# 2__Inverter.net
KiCad netlist of a schematic drawn in Altium Designer
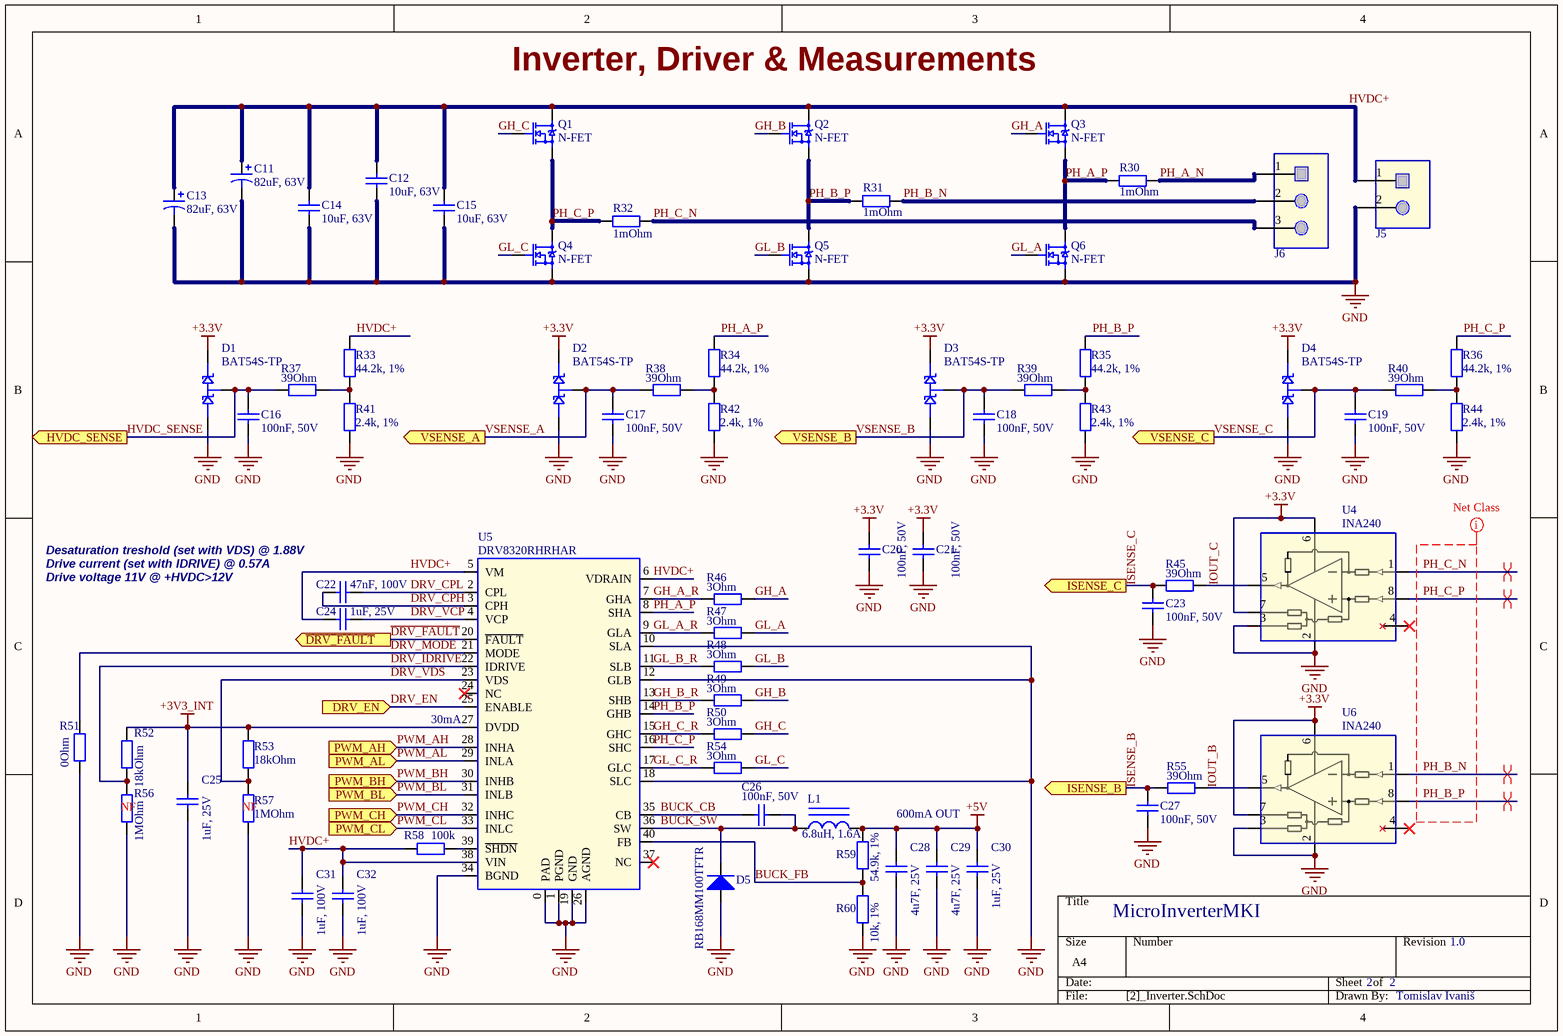
[diagram p0: [2]_Inverter.SchDoc]

(export (version "E")
  (design (tool "Eeschema 10.0.6"))
  (components
    (comp (ref "C11")
      (value "82uF, 63V")
      (footprint "CAP_H10")
      (description "Capacitor Polarized")
      (fields (field (name "MANUFACTURER PART NUMBER") "HHXC630ARA820MJA0G"))
      (libsource (lib "MyComponentLib") (part "Cap Pol"))
    )
    (comp (ref "C12")
      (value "10uF, 63V")
      (footprint "1210")
      (description "Capacitor")
      (fields (field (name "MANUFACTURER PART NUMBER") "GRM32ER71J106KA12L"))
      (libsource (lib "MyComponentLib") (part "Cap Semi"))
    )
    (comp (ref "C13")
      (value "82uF, 63V")
      (footprint "CAP_H10")
      (description "Capacitor Polarized")
      (fields (field (name "MANUFACTURER PART NUMBER") "HHXC630ARA820MJA0G"))
      (libsource (lib "MyComponentLib") (part "Cap Pol"))
    )
    (comp (ref "C14")
      (value "10uF, 63V")
      (footprint "1210")
      (description "Capacitor")
      (fields (field (name "MANUFACTURER PART NUMBER") "GRM32ER71J106KA12L"))
      (libsource (lib "MyComponentLib") (part "Cap Semi"))
    )
    (comp (ref "C15")
      (value "10uF, 63V")
      (footprint "1210")
      (description "Capacitor")
      (fields (field (name "MANUFACTURER PART NUMBER") "GRM32ER71J106KA12L"))
      (libsource (lib "MyComponentLib") (part "Cap Semi"))
    )
    (comp (ref "C16")
      (value "100nF, 50V")
      (footprint "0603")
      (description "Capacitor")
      (fields (field (name "MANUFACTURER PART NUMBER") "C0603C104M5RACTU"))
      (libsource (lib "MyComponentLib") (part "Cap Semi"))
    )
    (comp (ref "C17")
      (value "100nF, 50V")
      (footprint "0603")
      (description "Capacitor")
      (fields (field (name "MANUFACTURER PART NUMBER") "C0603C104M5RACTU"))
      (libsource (lib "MyComponentLib") (part "Cap Semi"))
    )
    (comp (ref "C18")
      (value "100nF, 50V")
      (footprint "0603")
      (description "Capacitor")
      (fields (field (name "MANUFACTURER PART NUMBER") "C0603C104M5RACTU"))
      (libsource (lib "MyComponentLib") (part "Cap Semi"))
    )
    (comp (ref "C19")
      (value "100nF, 50V")
      (footprint "0603")
      (description "Capacitor")
      (fields (field (name "MANUFACTURER PART NUMBER") "C0603C104M5RACTU"))
      (libsource (lib "MyComponentLib") (part "Cap Semi"))
    )
    (comp (ref "C20")
      (value "100nF, 50V")
      (footprint "0603")
      (description "Capacitor")
      (fields (field (name "MANUFACTURER PART NUMBER") "C0603C104M5RACTU"))
      (libsource (lib "MyComponentLib") (part "Cap Semi"))
    )
    (comp (ref "C21")
      (value "100nF, 50V")
      (footprint "0603")
      (description "Capacitor")
      (fields (field (name "MANUFACTURER PART NUMBER") "C0603C104M5RACTU"))
      (libsource (lib "MyComponentLib") (part "Cap Semi"))
    )
    (comp (ref "C22")
      (value "47nF, 100V")
      (footprint "0805")
      (description "Capacitor")
      (fields (field (name "MANUFACTURER PART NUMBER") "CC0805KKX7R0BB473"))
      (libsource (lib "MyComponentLib") (part "Cap Semi"))
    )
    (comp (ref "C23")
      (value "100nF, 50V")
      (footprint "0603")
      (description "Capacitor")
      (fields (field (name "MANUFACTURER PART NUMBER") "C0603C104M5RACTU"))
      (libsource (lib "MyComponentLib") (part "Cap Semi"))
    )
    (comp (ref "C24")
      (value "1uF, 25V")
      (footprint "0805")
      (description "Capacitor")
      (fields (field (name "MANUFACTURER PART NUMBER") "VJ0805Y105KXXTW1BC"))
      (libsource (lib "MyComponentLib") (part "Cap Semi"))
    )
    (comp (ref "C25")
      (value "1uF, 25V")
      (footprint "0805")
      (description "Capacitor")
      (fields (field (name "MANUFACTURER PART NUMBER") "VJ0805Y105KXXTW1BC"))
      (libsource (lib "MyComponentLib") (part "Cap Semi"))
    )
    (comp (ref "C26")
      (value "100nF, 50V")
      (footprint "0603")
      (description "Capacitor")
      (fields (field (name "MANUFACTURER PART NUMBER") "C0603C104M5RACTU"))
      (libsource (lib "MyComponentLib") (part "Cap Semi"))
    )
    (comp (ref "C27")
      (value "100nF, 50V")
      (footprint "0603")
      (description "Capacitor")
      (fields (field (name "MANUFACTURER PART NUMBER") "C0603C104M5RACTU"))
      (libsource (lib "MyComponentLib") (part "Cap Semi"))
    )
    (comp (ref "C28")
      (value "4u7F, 25V")
      (footprint "0805")
      (description "Capacitor")
      (fields (field (name "MANUFACTURER PART NUMBER") "885012107018"))
      (libsource (lib "MyComponentLib") (part "Cap Semi"))
    )
    (comp (ref "C29")
      (value "4u7F, 25V")
      (footprint "0805")
      (description "Capacitor")
      (fields (field (name "MANUFACTURER PART NUMBER") "885012107018"))
      (libsource (lib "MyComponentLib") (part "Cap Semi"))
    )
    (comp (ref "C30")
      (value "1uF, 25V")
      (footprint "0805")
      (description "Capacitor")
      (fields (field (name "MANUFACTURER PART NUMBER") "VJ0805Y105KXXTW1BC"))
      (libsource (lib "MyComponentLib") (part "Cap Semi"))
    )
    (comp (ref "C31")
      (value "1uF, 100V")
      (footprint "0805")
      (description "Capacitor")
      (fields (field (name "MANUFACTURER PART NUMBER") "HMK212BBJ105KG-TE"))
      (libsource (lib "MyComponentLib") (part "Cap Semi"))
    )
    (comp (ref "C32")
      (value "1uF, 100V")
      (footprint "0805")
      (description "Capacitor")
      (fields (field (name "MANUFACTURER PART NUMBER") "HMK212BBJ105KG-TE"))
      (libsource (lib "MyComponentLib") (part "Cap Semi"))
    )
    (comp (ref "D1")
      (value "BAT54S-TP")
      (footprint "SOT 23")
      (libsource (lib "MyComponentLib") (part "BAT54S-TP"))
    )
    (comp (ref "D2")
      (value "BAT54S-TP")
      (footprint "SOT 23")
      (libsource (lib "MyComponentLib") (part "BAT54S-TP"))
    )
    (comp (ref "D3")
      (value "BAT54S-TP")
      (footprint "SOT 23")
      (libsource (lib "MyComponentLib") (part "BAT54S-TP"))
    )
    (comp (ref "D4")
      (value "BAT54S-TP")
      (footprint "SOT 23")
      (libsource (lib "MyComponentLib") (part "BAT54S-TP"))
    )
    (comp (ref "D5")
      (value "RB168MM100TFTR")
      (footprint "SOD123")
      (libsource (lib "MyComponentLib") (part "Diode"))
    )
    (comp (ref "J5")
      (value "TERMINAL 2")
      (footprint "TERMINAL 2 POS")
      (description "TERMINAL BLOCK 2 POS")
      (libsource (lib "MyComponentLib") (part "TERMINAL 2"))
    )
    (comp (ref "J6")
      (value "TERMINAL 3")
      (footprint "TERMINAL 3 POS")
      (description "TERMINAL BLOCK 3 POS")
      (libsource (lib "MyComponentLib") (part "TERMINAL 3"))
    )
    (comp (ref "L1")
      (value "6.8uH, 1.6A")
      (footprint "INDUCTOR - 4x4 mm")
      (description "Magnetic-Core Inductor")
      (fields (field (name "MANUFACTURER PART NUMBER") "TYS40306R8M-10"))
      (libsource (lib "MyComponentLib") (part "Inductor Iron"))
    )
    (comp (ref "Q1")
      (value "N-FET")
      (footprint "SO-8FL")
      (fields (field (name "MANUFACTURER PART NUMBER") "NVMFS6H800NT1G"))
      (libsource (lib "MyComponentLib") (part "N-FET"))
    )
    (comp (ref "Q2")
      (value "N-FET")
      (footprint "SO-8FL")
      (fields (field (name "MANUFACTURER PART NUMBER") "NVMFS6H800NT1G"))
      (libsource (lib "MyComponentLib") (part "N-FET"))
    )
    (comp (ref "Q3")
      (value "N-FET")
      (footprint "SO-8FL")
      (fields (field (name "MANUFACTURER PART NUMBER") "NVMFS6H800NT1G"))
      (libsource (lib "MyComponentLib") (part "N-FET"))
    )
    (comp (ref "Q4")
      (value "N-FET")
      (footprint "SO-8FL")
      (fields (field (name "MANUFACTURER PART NUMBER") "NVMFS6H800NT1G"))
      (libsource (lib "MyComponentLib") (part "N-FET"))
    )
    (comp (ref "Q5")
      (value "N-FET")
      (footprint "SO-8FL")
      (fields (field (name "MANUFACTURER PART NUMBER") "NVMFS6H800NT1G"))
      (libsource (lib "MyComponentLib") (part "N-FET"))
    )
    (comp (ref "Q6")
      (value "N-FET")
      (footprint "SO-8FL")
      (fields (field (name "MANUFACTURER PART NUMBER") "NVMFS6H800NT1G"))
      (libsource (lib "MyComponentLib") (part "N-FET"))
    )
    (comp (ref "R30")
      (value "1mOhm")
      (footprint "RES TLR2HW CURRENT SENSE")
      (description "Resistor")
      (fields (field (name "MANUFACTURER PART NUMBER") "TLR2HWDTE1L00F50"))
      (libsource (lib "") (part "Res_1"))
    )
    (comp (ref "R31")
      (value "1mOhm")
      (footprint "RES TLR2HW CURRENT SENSE")
      (description "Resistor")
      (fields (field (name "MANUFACTURER PART NUMBER") "TLR2HWDTE1L00F50"))
      (libsource (lib "") (part "Res_1"))
    )
    (comp (ref "R32")
      (value "1mOhm")
      (footprint "RES TLR2HW CURRENT SENSE")
      (description "Resistor")
      (fields (field (name "MANUFACTURER PART NUMBER") "TLR2HWDTE1L00F50"))
      (libsource (lib "") (part "Res_1"))
    )
    (comp (ref "R33")
      (value "44.2k, 1%")
      (footprint "0805")
      (description "Resistor")
      (fields (field (name "MANUFACTURER PART NUMBER") "CR0805-FX-4422ELF"))
      (libsource (lib "MyComponentLib") (part "Res"))
    )
    (comp (ref "R34")
      (value "44.2k, 1%")
      (footprint "0805")
      (description "Resistor")
      (fields (field (name "MANUFACTURER PART NUMBER") "CR0805-FX-4422ELF"))
      (libsource (lib "MyComponentLib") (part "Res"))
    )
    (comp (ref "R35")
      (value "44.2k, 1%")
      (footprint "0805")
      (description "Resistor")
      (fields (field (name "MANUFACTURER PART NUMBER") "CR0805-FX-4422ELF"))
      (libsource (lib "MyComponentLib") (part "Res"))
    )
    (comp (ref "R36")
      (value "44.2k, 1%")
      (footprint "0805")
      (description "Resistor")
      (fields (field (name "MANUFACTURER PART NUMBER") "CR0805-FX-4422ELF"))
      (libsource (lib "MyComponentLib") (part "Res"))
    )
    (comp (ref "R37")
      (value "39Ohm")
      (footprint "0805")
      (description "Resistor")
      (fields (field (name "MANUFACTURER PART NUMBER") "CR0805-JW-390ELF"))
      (libsource (lib "") (part "Res_1"))
    )
    (comp (ref "R38")
      (value "39Ohm")
      (footprint "0805")
      (description "Resistor")
      (fields (field (name "MANUFACTURER PART NUMBER") "CR0805-JW-390ELF"))
      (libsource (lib "") (part "Res_1"))
    )
    (comp (ref "R39")
      (value "39Ohm")
      (footprint "0805")
      (description "Resistor")
      (fields (field (name "MANUFACTURER PART NUMBER") "CR0805-JW-390ELF"))
      (libsource (lib "") (part "Res_1"))
    )
    (comp (ref "R40")
      (value "39Ohm")
      (footprint "0805")
      (description "Resistor")
      (fields (field (name "MANUFACTURER PART NUMBER") "CR0805-JW-390ELF"))
      (libsource (lib "") (part "Res_1"))
    )
    (comp (ref "R41")
      (value "2.4k, 1%")
      (footprint "0805")
      (description "Resistor")
      (fields (field (name "MANUFACTURER PART NUMBER") "CR0805-FX-2401ELF"))
      (libsource (lib "MyComponentLib") (part "Res"))
    )
    (comp (ref "R42")
      (value "2.4k, 1%")
      (footprint "0805")
      (description "Resistor")
      (fields (field (name "MANUFACTURER PART NUMBER") "CR0805-FX-2401ELF"))
      (libsource (lib "MyComponentLib") (part "Res"))
    )
    (comp (ref "R43")
      (value "2.4k, 1%")
      (footprint "0805")
      (description "Resistor")
      (fields (field (name "MANUFACTURER PART NUMBER") "CR0805-FX-2401ELF"))
      (libsource (lib "MyComponentLib") (part "Res"))
    )
    (comp (ref "R44")
      (value "2.4k, 1%")
      (footprint "0805")
      (description "Resistor")
      (fields (field (name "MANUFACTURER PART NUMBER") "CR0805-FX-2401ELF"))
      (libsource (lib "MyComponentLib") (part "Res"))
    )
    (comp (ref "R45")
      (value "39Ohm")
      (footprint "0805")
      (description "Resistor")
      (fields (field (name "MANUFACTURER PART NUMBER") "CR0805-JW-390ELF"))
      (libsource (lib "") (part "Res_1"))
    )
    (comp (ref "R46")
      (value "3Ohm")
      (footprint "0805")
      (description "Resistor")
      (fields (field (name "MANUFACTURER PART NUMBER") "SG73P2ATTD3R00F"))
      (libsource (lib "") (part "Res_1"))
    )
    (comp (ref "R47")
      (value "3Ohm")
      (footprint "0805")
      (description "Resistor")
      (fields (field (name "MANUFACTURER PART NUMBER") "SG73P2ATTD3R00F"))
      (libsource (lib "") (part "Res_1"))
    )
    (comp (ref "R48")
      (value "3Ohm")
      (footprint "0805")
      (description "Resistor")
      (fields (field (name "MANUFACTURER PART NUMBER") "SG73P2ATTD3R00F"))
      (libsource (lib "") (part "Res_1"))
    )
    (comp (ref "R49")
      (value "3Ohm")
      (footprint "0805")
      (description "Resistor")
      (fields (field (name "MANUFACTURER PART NUMBER") "SG73P2ATTD3R00F"))
      (libsource (lib "") (part "Res_1"))
    )
    (comp (ref "R50")
      (value "3Ohm")
      (footprint "0805")
      (description "Resistor")
      (fields (field (name "MANUFACTURER PART NUMBER") "SG73P2ATTD3R00F"))
      (libsource (lib "") (part "Res_1"))
    )
    (comp (ref "R51")
      (value "0Ohm")
      (footprint "0805")
      (description "Resistor")
      (fields (field (name "MANUFACTURER PART NUMBER") "CR0805-J/-000ELF"))
      (libsource (lib "MyComponentLib") (part "Res"))
    )
    (comp (ref "R52")
      (value "18kOhm")
      (footprint "0805")
      (description "Resistor")
      (fields (field (name "MANUFACTURER PART NUMBER") "CR0805-FX-1802ELF"))
      (libsource (lib "MyComponentLib") (part "Res"))
    )
    (comp (ref "R53")
      (value "18kOhm")
      (footprint "0805")
      (description "Resistor")
      (fields (field (name "MANUFACTURER PART NUMBER") "CR0805-FX-1802ELF"))
      (libsource (lib "MyComponentLib") (part "Res"))
    )
    (comp (ref "R54")
      (value "3Ohm")
      (footprint "0805")
      (description "Resistor")
      (fields (field (name "MANUFACTURER PART NUMBER") "SG73P2ATTD3R00F"))
      (libsource (lib "") (part "Res_1"))
    )
    (comp (ref "R55")
      (value "39Ohm")
      (footprint "0805")
      (description "Resistor")
      (fields (field (name "MANUFACTURER PART NUMBER") "CR0805-JW-390ELF"))
      (libsource (lib "") (part "Res_1"))
    )
    (comp (ref "R56")
      (value "1MOhm")
      (footprint "0805")
      (description "Resistor")
      (fields (field (name "MANUFACTURER PART NUMBER") "CR0805-FW-1005ELF"))
      (libsource (lib "MyComponentLib") (part "Res"))
    )
    (comp (ref "R57")
      (value "1MOhm")
      (footprint "0805")
      (description "Resistor")
      (fields (field (name "MANUFACTURER PART NUMBER") "CR0805-FW-1005ELF"))
      (libsource (lib "MyComponentLib") (part "Res"))
    )
    (comp (ref "R58")
      (value "100k")
      (footprint "0805")
      (description "Resistor")
      (fields (field (name "MANUFACTURER PART NUMBER") "CR0805-FX-1003ELF"))
      (libsource (lib "") (part "Res_2"))
    )
    (comp (ref "R59")
      (value "54.9k, 1%")
      (footprint "0805")
      (description "Resistor")
      (fields (field (name "MANUFACTURER PART NUMBER") "CR0805-FX-5492ELF"))
      (libsource (lib "MyComponentLib") (part "Res"))
    )
    (comp (ref "R60")
      (value "10k, 1%")
      (footprint "0805")
      (description "Resistor")
      (fields (field (name "MANUFACTURER PART NUMBER") "CR0805-FX-1002ELF"))
      (libsource (lib "MyComponentLib") (part "Res"))
    )
    (comp (ref "U4")
      (value "INA240")
      (footprint "SO 8 - HighDensity")
      (fields (field (name "MANUFACTURER PART NUMBER") "INA240A2DR"))
      (libsource (lib "MyComponentLib") (part "INA240"))
    )
    (comp (ref "U5")
      (value "DRV8320RHRHAR")
      (footprint "VQFN-40")
      (description "3f Gate driver 60V")
      (libsource (lib "MyComponentLib") (part "DRV8320RHRHAR"))
    )
    (comp (ref "U6")
      (value "INA240")
      (footprint "SO 8 - HighDensity")
      (fields (field (name "MANUFACTURER PART NUMBER") "INA240A2DR"))
      (libsource (lib "MyComponentLib") (part "INA240"))
    )
  )
  (nets
    (net (code "1") (name "+3.3V") (class "Default")
      (node (ref "C20") (pin "1") (pinfunction "1_1") (pintype "passive"))
      (node (ref "C21") (pin "1") (pinfunction "1_1") (pintype "passive"))
      (node (ref "D1") (pin "3") (pinfunction "K_3") (pintype "passive"))
      (node (ref "D2") (pin "3") (pinfunction "K_3") (pintype "passive"))
      (node (ref "D3") (pin "3") (pinfunction "K_3") (pintype "passive"))
      (node (ref "D4") (pin "3") (pinfunction "K_3") (pintype "passive"))
      (node (ref "U4") (pin "6") (pinfunction "*_6") (pintype "passive"))
      (node (ref "U4") (pin "7") (pinfunction "*_7") (pintype "passive"))
      (node (ref "U6") (pin "6") (pinfunction "*_6") (pintype "passive"))
      (node (ref "U6") (pin "7") (pinfunction "*_7") (pintype "passive"))
    )
    (net (code "2") (name "+3V3_INT") (class "Default")
      (node (ref "C25") (pin "1") (pinfunction "1_1") (pintype "passive"))
      (node (ref "R52") (pin "2") (pinfunction "2_2") (pintype "passive"))
      (node (ref "R53") (pin "2") (pinfunction "2_2") (pintype "passive"))
      (node (ref "U5") (pin "27") (pinfunction "DVDD_27") (pintype "passive"))
    )
    (net (code "3") (name "+5V") (class "Default")
      (node (ref "C28") (pin "1") (pinfunction "1_1") (pintype "passive"))
      (node (ref "C29") (pin "1") (pinfunction "1_1") (pintype "passive"))
      (node (ref "C30") (pin "1") (pinfunction "1_1") (pintype "passive"))
      (node (ref "L1") (pin "2") (pinfunction "2_2") (pintype "passive"))
      (node (ref "R59") (pin "2") (pinfunction "2_2") (pintype "passive"))
    )
    (net (code "4") (name "/BUCK_CB") (class "Default")
      (node (ref "C26") (pin "2") (pinfunction "2_2") (pintype "passive"))
      (node (ref "U5") (pin "35") (pinfunction "CB_35") (pintype "passive"))
    )
    (net (code "5") (name "/BUCK_FB") (class "Default")
      (node (ref "R59") (pin "1") (pinfunction "1_1") (pintype "passive"))
      (node (ref "R60") (pin "2") (pinfunction "2_2") (pintype "passive"))
      (node (ref "U5") (pin "40") (pinfunction "FB_40") (pintype "passive"))
    )
    (net (code "6") (name "/BUCK_SW") (class "Default")
      (node (ref "C26") (pin "1") (pinfunction "1_1") (pintype "passive"))
      (node (ref "D5") (pin "2") (pinfunction "K_2") (pintype "passive"))
      (node (ref "L1") (pin "1") (pinfunction "1_1") (pintype "passive"))
      (node (ref "U5") (pin "36") (pinfunction "SW_36") (pintype "passive"))
    )
    (net (code "7") (name "/DRV_CPH") (class "Default")
      (node (ref "C22") (pin "1") (pinfunction "1_1") (pintype "passive"))
      (node (ref "U5") (pin "3") (pinfunction "CPH_3") (pintype "passive"))
    )
    (net (code "8") (name "/DRV_CPL") (class "Default")
      (node (ref "C22") (pin "2") (pinfunction "2_2") (pintype "passive"))
      (node (ref "U5") (pin "2") (pinfunction "CPL_2") (pintype "passive"))
    )
    (net (code "9") (name "/DRV_EN") (class "Default")
      (node (ref "U5") (pin "25") (pinfunction "ENABLE_25") (pintype "passive"))
    )
    (net (code "10") (name "/DRV_IDRIVE") (class "Default")
      (node (ref "R52") (pin "1") (pinfunction "1_1") (pintype "passive"))
      (node (ref "R56") (pin "2") (pinfunction "2_2") (pintype "passive"))
      (node (ref "U5") (pin "22") (pinfunction "IDRIVE_22") (pintype "passive"))
    )
    (net (code "11") (name "/DRV_MODE") (class "Default")
      (node (ref "R51") (pin "2") (pinfunction "2_2") (pintype "passive"))
      (node (ref "U5") (pin "21") (pinfunction "MODE_21") (pintype "passive"))
    )
    (net (code "12") (name "/DRV_VCP") (class "Default")
      (node (ref "C24") (pin "1") (pinfunction "1_1") (pintype "passive"))
      (node (ref "U5") (pin "4") (pinfunction "VCP_4") (pintype "passive"))
    )
    (net (code "13") (name "/DRV_VDS") (class "Default")
      (node (ref "R53") (pin "1") (pinfunction "1_1") (pintype "passive"))
      (node (ref "R57") (pin "2") (pinfunction "2_2") (pintype "passive"))
      (node (ref "U5") (pin "23") (pinfunction "VDS_23") (pintype "passive"))
    )
    (net (code "14") (name "/GH_A") (class "Default")
      (node (ref "Q3") (pin "1") (pintype "passive"))
      (node (ref "R46") (pin "2") (pinfunction "2_2") (pintype "passive"))
    )
    (net (code "15") (name "/GH_A_R") (class "Default")
      (node (ref "R46") (pin "1") (pinfunction "1_1") (pintype "passive"))
      (node (ref "U5") (pin "7") (pinfunction "GHA_7") (pintype "passive"))
    )
    (net (code "16") (name "/GH_B") (class "Default")
      (node (ref "Q2") (pin "1") (pintype "passive"))
      (node (ref "R49") (pin "2") (pinfunction "2_2") (pintype "passive"))
    )
    (net (code "17") (name "/GH_B_R") (class "Default")
      (node (ref "R49") (pin "1") (pinfunction "1_1") (pintype "passive"))
      (node (ref "U5") (pin "13") (pinfunction "SHB_13") (pintype "passive"))
    )
    (net (code "18") (name "/GH_C") (class "Default")
      (node (ref "Q1") (pin "1") (pintype "passive"))
      (node (ref "R50") (pin "2") (pinfunction "2_2") (pintype "passive"))
    )
    (net (code "19") (name "/GH_C_R") (class "Default")
      (node (ref "R50") (pin "1") (pinfunction "1_1") (pintype "passive"))
      (node (ref "U5") (pin "15") (pinfunction "GHC_15") (pintype "passive"))
    )
    (net (code "20") (name "/GL_A") (class "Default")
      (node (ref "Q6") (pin "1") (pintype "passive"))
      (node (ref "R47") (pin "2") (pinfunction "2_2") (pintype "passive"))
    )
    (net (code "21") (name "/GL_A_R") (class "Default")
      (node (ref "R47") (pin "1") (pinfunction "1_1") (pintype "passive"))
      (node (ref "U5") (pin "9") (pinfunction "GLA_9") (pintype "passive"))
    )
    (net (code "22") (name "/GL_B") (class "Default")
      (node (ref "Q5") (pin "1") (pintype "passive"))
      (node (ref "R48") (pin "2") (pinfunction "2_2") (pintype "passive"))
    )
    (net (code "23") (name "/GL_B_R") (class "Default")
      (node (ref "R48") (pin "1") (pinfunction "1_1") (pintype "passive"))
      (node (ref "U5") (pin "11") (pinfunction "SLB_11") (pintype "passive"))
    )
    (net (code "24") (name "/GL_C") (class "Default")
      (node (ref "Q4") (pin "1") (pintype "passive"))
      (node (ref "R54") (pin "2") (pinfunction "2_2") (pintype "passive"))
    )
    (net (code "25") (name "/GL_C_R") (class "Default")
      (node (ref "R54") (pin "1") (pinfunction "1_1") (pintype "passive"))
      (node (ref "U5") (pin "17") (pinfunction "GLC_17") (pintype "passive"))
    )
    (net (code "26") (name "/HVDC+") (class "Default")
      (node (ref "C11") (pin "2") (pinfunction "1_2") (pintype "passive"))
      (node (ref "C12") (pin "1") (pinfunction "1_1") (pintype "passive"))
      (node (ref "C13") (pin "2") (pinfunction "1_2") (pintype "passive"))
      (node (ref "C14") (pin "1") (pinfunction "1_1") (pintype "passive"))
      (node (ref "C15") (pin "1") (pinfunction "1_1") (pintype "passive"))
      (node (ref "C24") (pin "2") (pinfunction "2_2") (pintype "passive"))
      (node (ref "C31") (pin "1") (pinfunction "1_1") (pintype "passive"))
      (node (ref "C32") (pin "1") (pinfunction "1_1") (pintype "passive"))
      (node (ref "J5") (pin "1") (pinfunction "1_1") (pintype "passive"))
      (node (ref "Q1") (pin "2") (pintype "passive"))
      (node (ref "Q2") (pin "2") (pintype "passive"))
      (node (ref "Q3") (pin "2") (pintype "passive"))
      (node (ref "R33") (pin "2") (pinfunction "2_2") (pintype "passive"))
      (node (ref "R58") (pin "2") (pinfunction "2_2") (pintype "passive"))
      (node (ref "U5") (pin "38") (pinfunction "VIN_38") (pintype "passive"))
      (node (ref "U5") (pin "5") (pinfunction "VM_5") (pintype "passive"))
      (node (ref "U5") (pin "6") (pinfunction "VDRAIN_6") (pintype "passive"))
    )
    (net (code "27") (name "/HVDC_SENSE") (class "Default")
      (node (ref "C16") (pin "1") (pinfunction "1_1") (pintype "passive"))
      (node (ref "D1") (pin "1") (pinfunction "KA_1") (pintype "passive"))
      (node (ref "R37") (pin "1") (pinfunction "1_1") (pintype "passive"))
    )
    (net (code "28") (name "/IOUT_B") (class "Default")
      (node (ref "R55") (pin "2") (pinfunction "2_2") (pintype "passive"))
      (node (ref "U6") (pin "5") (pinfunction "OUT_5") (pintype "output"))
    )
    (net (code "29") (name "/IOUT_C") (class "Default")
      (node (ref "R45") (pin "2") (pinfunction "2_2") (pintype "passive"))
      (node (ref "U4") (pin "5") (pinfunction "OUT_5") (pintype "output"))
    )
    (net (code "30") (name "/ISENSE_B") (class "Default")
      (node (ref "C27") (pin "1") (pinfunction "1_1") (pintype "passive"))
      (node (ref "R55") (pin "1") (pinfunction "1_1") (pintype "passive"))
    )
    (net (code "31") (name "/ISENSE_C") (class "Default")
      (node (ref "C23") (pin "1") (pinfunction "1_1") (pintype "passive"))
      (node (ref "R45") (pin "1") (pinfunction "1_1") (pintype "passive"))
    )
    (net (code "32") (name "/PH_A_N") (class "Default")
      (node (ref "J6") (pin "1") (pinfunction "1_1") (pintype "passive"))
      (node (ref "R30") (pin "2") (pinfunction "2_2") (pintype "passive"))
    )
    (net (code "33") (name "/PH_A_P") (class "Default")
      (node (ref "Q3") (pin "3") (pintype "passive"))
      (node (ref "Q6") (pin "2") (pintype "passive"))
      (node (ref "R30") (pin "1") (pinfunction "1_1") (pintype "passive"))
      (node (ref "R34") (pin "2") (pinfunction "2_2") (pintype "passive"))
      (node (ref "U5") (pin "8") (pinfunction "SHA_8") (pintype "passive"))
    )
    (net (code "34") (name "/PH_B_N") (class "Default")
      (node (ref "J6") (pin "2") (pinfunction "2_2") (pintype "passive"))
      (node (ref "R31") (pin "2") (pinfunction "2_2") (pintype "passive"))
      (node (ref "U6") (pin "1") (pinfunction "IN-_1") (pintype "input"))
    )
    (net (code "35") (name "/PH_B_P") (class "Default")
      (node (ref "Q2") (pin "3") (pintype "passive"))
      (node (ref "Q5") (pin "2") (pintype "passive"))
      (node (ref "R31") (pin "1") (pinfunction "1_1") (pintype "passive"))
      (node (ref "R35") (pin "2") (pinfunction "2_2") (pintype "passive"))
      (node (ref "U5") (pin "14") (pinfunction "GHB_14") (pintype "passive"))
      (node (ref "U6") (pin "8") (pinfunction "IN+_8") (pintype "input"))
    )
    (net (code "36") (name "/PH_C_N") (class "Default")
      (node (ref "J6") (pin "3") (pinfunction "3_3") (pintype "passive"))
      (node (ref "R32") (pin "2") (pinfunction "2_2") (pintype "passive"))
      (node (ref "U4") (pin "1") (pinfunction "IN-_1") (pintype "input"))
    )
    (net (code "37") (name "/PH_C_P") (class "Default")
      (node (ref "Q1") (pin "3") (pintype "passive"))
      (node (ref "Q4") (pin "2") (pintype "passive"))
      (node (ref "R32") (pin "1") (pinfunction "1_1") (pintype "passive"))
      (node (ref "R36") (pin "2") (pinfunction "2_2") (pintype "passive"))
      (node (ref "U4") (pin "8") (pinfunction "IN+_8") (pintype "input"))
      (node (ref "U5") (pin "16") (pinfunction "SHC_16") (pintype "passive"))
    )
    (net (code "38") (name "/PWM_AH") (class "Default")
      (node (ref "U5") (pin "28") (pinfunction "INHA_28") (pintype "passive"))
    )
    (net (code "39") (name "/PWM_AL") (class "Default")
      (node (ref "U5") (pin "29") (pinfunction "INLA_29") (pintype "passive"))
    )
    (net (code "40") (name "/PWM_BH") (class "Default")
      (node (ref "U5") (pin "30") (pinfunction "INHB_30") (pintype "passive"))
    )
    (net (code "41") (name "/PWM_BL") (class "Default")
      (node (ref "U5") (pin "31") (pinfunction "INLB_31") (pintype "passive"))
    )
    (net (code "42") (name "/PWM_CH") (class "Default")
      (node (ref "U5") (pin "32") (pinfunction "INHC_32") (pintype "passive"))
    )
    (net (code "43") (name "/PWM_CL") (class "Default")
      (node (ref "U5") (pin "33") (pinfunction "INLC_33") (pintype "passive"))
    )
    (net (code "44") (name "/VSENSE_A") (class "Default")
      (node (ref "C17") (pin "1") (pinfunction "1_1") (pintype "passive"))
      (node (ref "D2") (pin "1") (pinfunction "KA_1") (pintype "passive"))
      (node (ref "R38") (pin "1") (pinfunction "1_1") (pintype "passive"))
    )
    (net (code "45") (name "/VSENSE_B") (class "Default")
      (node (ref "C18") (pin "1") (pinfunction "1_1") (pintype "passive"))
      (node (ref "D3") (pin "1") (pinfunction "KA_1") (pintype "passive"))
      (node (ref "R39") (pin "1") (pinfunction "1_1") (pintype "passive"))
    )
    (net (code "46") (name "/VSENSE_C") (class "Default")
      (node (ref "C19") (pin "1") (pinfunction "1_1") (pintype "passive"))
      (node (ref "D4") (pin "1") (pinfunction "KA_1") (pintype "passive"))
      (node (ref "R40") (pin "1") (pinfunction "1_1") (pintype "passive"))
    )
    (net (code "47") (name "/~{DRV_FAULT}") (class "Default")
      (node (ref "U5") (pin "20") (pinfunction "~{FAULT}_20") (pintype "passive"))
    )
    (net (code "48") (name "GND") (class "Default")
      (node (ref "C11") (pin "1") (pinfunction "2_1") (pintype "passive"))
      (node (ref "C12") (pin "2") (pinfunction "2_2") (pintype "passive"))
      (node (ref "C13") (pin "1") (pinfunction "2_1") (pintype "passive"))
      (node (ref "C14") (pin "2") (pinfunction "2_2") (pintype "passive"))
      (node (ref "C15") (pin "2") (pinfunction "2_2") (pintype "passive"))
      (node (ref "C16") (pin "2") (pinfunction "2_2") (pintype "passive"))
      (node (ref "C17") (pin "2") (pinfunction "2_2") (pintype "passive"))
      (node (ref "C18") (pin "2") (pinfunction "2_2") (pintype "passive"))
      (node (ref "C19") (pin "2") (pinfunction "2_2") (pintype "passive"))
      (node (ref "C20") (pin "2") (pinfunction "2_2") (pintype "passive"))
      (node (ref "C21") (pin "2") (pinfunction "2_2") (pintype "passive"))
      (node (ref "C23") (pin "2") (pinfunction "2_2") (pintype "passive"))
      (node (ref "C25") (pin "2") (pinfunction "2_2") (pintype "passive"))
      (node (ref "C27") (pin "2") (pinfunction "2_2") (pintype "passive"))
      (node (ref "C28") (pin "2") (pinfunction "2_2") (pintype "passive"))
      (node (ref "C29") (pin "2") (pinfunction "2_2") (pintype "passive"))
      (node (ref "C30") (pin "2") (pinfunction "2_2") (pintype "passive"))
      (node (ref "C31") (pin "2") (pinfunction "2_2") (pintype "passive"))
      (node (ref "C32") (pin "2") (pinfunction "2_2") (pintype "passive"))
      (node (ref "D1") (pin "2") (pinfunction "A_2") (pintype "passive"))
      (node (ref "D2") (pin "2") (pinfunction "A_2") (pintype "passive"))
      (node (ref "D3") (pin "2") (pinfunction "A_2") (pintype "passive"))
      (node (ref "D4") (pin "2") (pinfunction "A_2") (pintype "passive"))
      (node (ref "D5") (pin "1") (pinfunction "A_1") (pintype "passive"))
      (node (ref "J5") (pin "2") (pinfunction "2_2") (pintype "passive"))
      (node (ref "Q4") (pin "3") (pintype "passive"))
      (node (ref "Q5") (pin "3") (pintype "passive"))
      (node (ref "Q6") (pin "3") (pintype "passive"))
      (node (ref "R41") (pin "1") (pinfunction "1_1") (pintype "passive"))
      (node (ref "R42") (pin "1") (pinfunction "1_1") (pintype "passive"))
      (node (ref "R43") (pin "1") (pinfunction "1_1") (pintype "passive"))
      (node (ref "R44") (pin "1") (pinfunction "1_1") (pintype "passive"))
      (node (ref "R51") (pin "1") (pinfunction "1_1") (pintype "passive"))
      (node (ref "R56") (pin "1") (pinfunction "1_1") (pintype "passive"))
      (node (ref "R57") (pin "1") (pinfunction "1_1") (pintype "passive"))
      (node (ref "R60") (pin "1") (pinfunction "1_1") (pintype "passive"))
      (node (ref "U4") (pin "2") (pinfunction "*_2") (pintype "passive"))
      (node (ref "U4") (pin "3") (pinfunction "*_3") (pintype "passive"))
      (node (ref "U5") (pin "0") (pinfunction "PAD_0") (pintype "passive"))
      (node (ref "U5") (pin "1") (pinfunction "PGND_1") (pintype "passive"))
      (node (ref "U5") (pin "10") (pinfunction "SLA_10") (pintype "passive"))
      (node (ref "U5") (pin "12") (pinfunction "GLB_12") (pintype "passive"))
      (node (ref "U5") (pin "18") (pinfunction "SLC_18") (pintype "passive"))
      (node (ref "U5") (pin "19") (pinfunction "GND_19") (pintype "passive"))
      (node (ref "U5") (pin "26") (pinfunction "AGND_26") (pintype "passive"))
      (node (ref "U5") (pin "34") (pinfunction "BGND_34") (pintype "passive"))
      (node (ref "U6") (pin "2") (pinfunction "*_2") (pintype "passive"))
      (node (ref "U6") (pin "3") (pinfunction "*_3") (pintype "passive"))
    )
    (net (code "49") (name "Net-(R33-Pad1)") (class "Default")
      (node (ref "R33") (pin "1") (pinfunction "1_1") (pintype "passive"))
      (node (ref "R37") (pin "2") (pinfunction "2_2") (pintype "passive"))
      (node (ref "R41") (pin "2") (pinfunction "2_2") (pintype "passive"))
    )
    (net (code "50") (name "Net-(R34-Pad1)") (class "Default")
      (node (ref "R34") (pin "1") (pinfunction "1_1") (pintype "passive"))
      (node (ref "R38") (pin "2") (pinfunction "2_2") (pintype "passive"))
      (node (ref "R42") (pin "2") (pinfunction "2_2") (pintype "passive"))
    )
    (net (code "51") (name "Net-(R35-Pad1)") (class "Default")
      (node (ref "R35") (pin "1") (pinfunction "1_1") (pintype "passive"))
      (node (ref "R39") (pin "2") (pinfunction "2_2") (pintype "passive"))
      (node (ref "R43") (pin "2") (pinfunction "2_2") (pintype "passive"))
    )
    (net (code "52") (name "Net-(R36-Pad1)") (class "Default")
      (node (ref "R36") (pin "1") (pinfunction "1_1") (pintype "passive"))
      (node (ref "R40") (pin "2") (pinfunction "2_2") (pintype "passive"))
      (node (ref "R44") (pin "2") (pinfunction "2_2") (pintype "passive"))
    )
    (net (code "53") (name "Net-(U5-~{SHDN})") (class "Default")
      (node (ref "R58") (pin "1") (pinfunction "1_1") (pintype "passive"))
      (node (ref "U5") (pin "39") (pinfunction "~{SHDN}_39") (pintype "passive"))
    )
    (net (code "54") (name "unconnected-(U4-NC-Pad4)") (class "Default")
      (node (ref "U4") (pin "4") (pinfunction "NC_4") (pintype "passive+no_connect"))
    )
    (net (code "55") (name "unconnected-(U5-NC-Pad24)") (class "Default")
      (node (ref "U5") (pin "24") (pinfunction "NC_24") (pintype "passive+no_connect"))
    )
    (net (code "56") (name "unconnected-(U5-NC-Pad37)") (class "Default")
      (node (ref "U5") (pin "37") (pinfunction "NC_37") (pintype "passive+no_connect"))
    )
    (net (code "57") (name "unconnected-(U6-NC-Pad4)") (class "Default")
      (node (ref "U6") (pin "4") (pinfunction "NC_4") (pintype "passive+no_connect"))
    )
  )
)
